# PROC091F_CAN_INTERFACE.net
KiCad netlist of a schematic drawn in Altium Designer
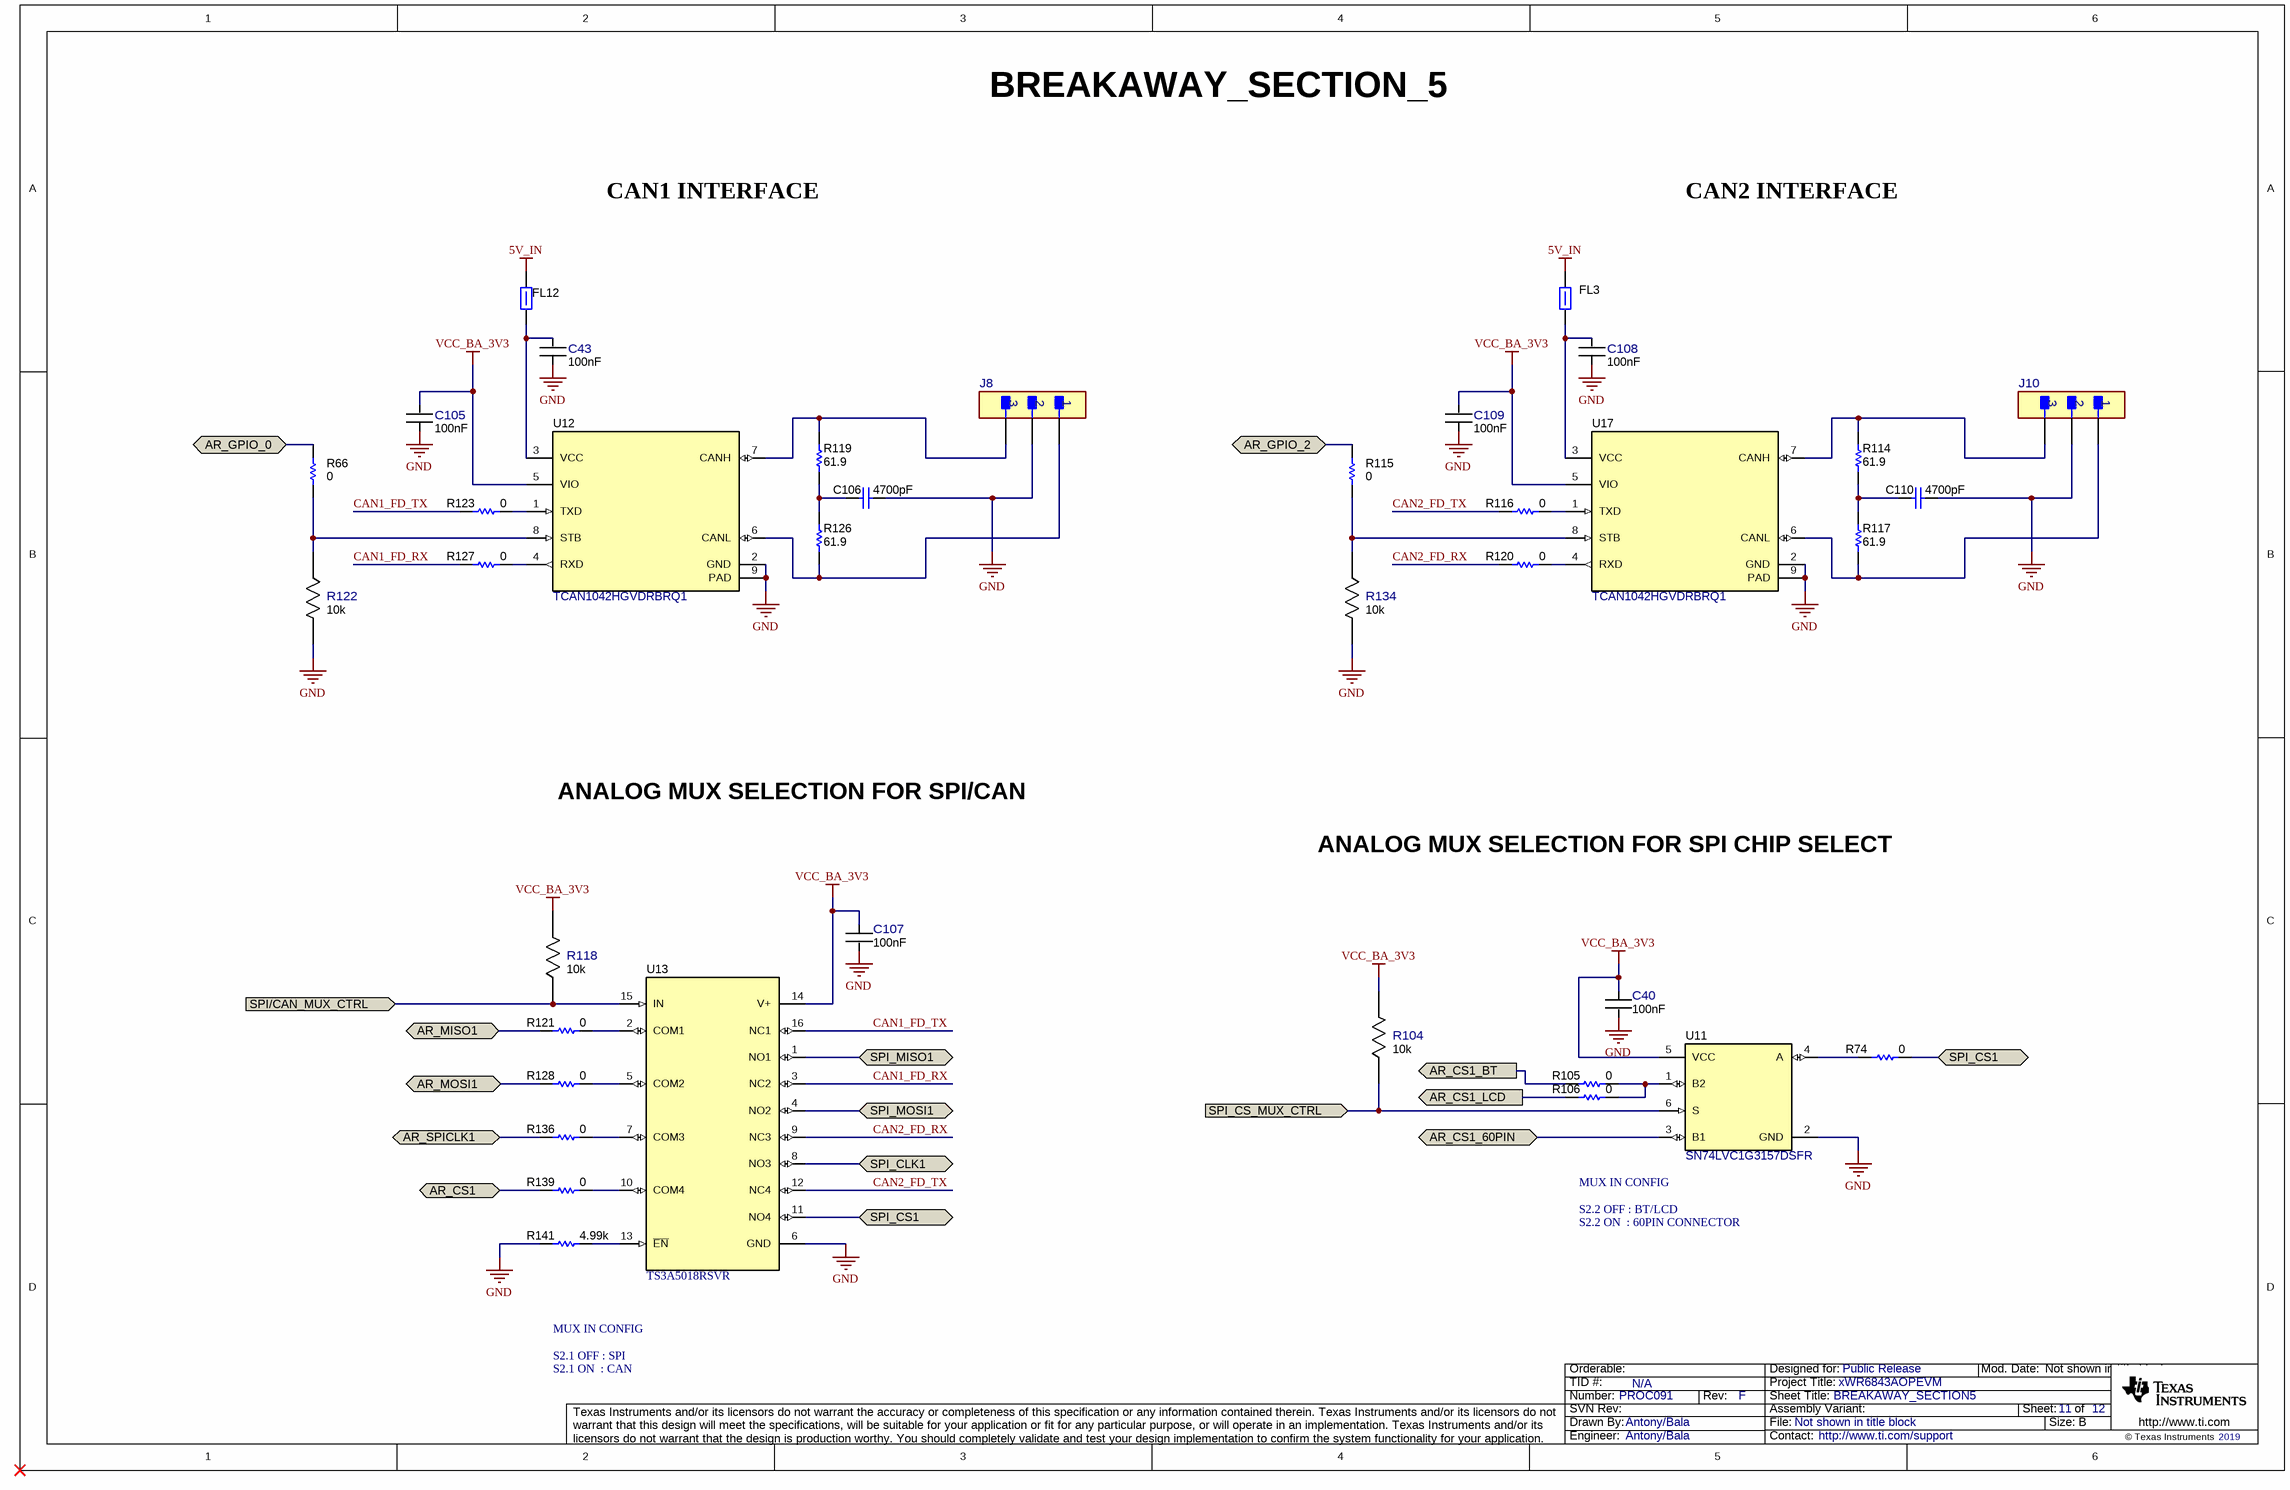
[diagram p0: PROC091F_CAN_INTERFACE.SchDoc]

(export (version "E")
  (design (tool "Eeschema 10.0.6"))
  (components
    (comp (ref "C40")
      (value "GRM033R6YA104KE14D")
      (footprint "FP-GRM033R6YA104KE14D_0201 (0603 Metric)-IPC_C")
      (description "Cap Ceramic 0.1uF 35V X5R 10% Pad SMD 0201 85C T/R")
      (fields (field (name "CAP_F") "100nF") (field (name "MANUFACTURER") "Murata Electronics North America"))
      (libsource (lib "Altium Vault - TI") (part "SYM-B32642B0223J"))
    )
    (comp (ref "C43")
      (value "GRM033R6YA104KE14D")
      (footprint "FP-GRM033R6YA104KE14D_0201 (0603 Metric)-IPC_C")
      (description "Cap Ceramic 0.1uF 35V X5R 10% Pad SMD 0201 85C T/R")
      (fields (field (name "CAP_F") "100nF") (field (name "MANUFACTURER") "Murata Electronics North America"))
      (libsource (lib "Altium Vault - TI") (part "SYM-B32642B0223J"))
    )
    (comp (ref "C105")
      (value "GRM033R6YA104KE14D")
      (footprint "FP-GRM033R6YA104KE14D_0201 (0603 Metric)-IPC_C")
      (description "Cap Ceramic 0.1uF 35V X5R 10% Pad SMD 0201 85C T/R")
      (fields (field (name "CAP_F") "100nF") (field (name "MANUFACTURER") "Murata Electronics North America"))
      (libsource (lib "Altium Vault - TI") (part "SYM-B32642B0223J"))
    )
    (comp (ref "C106")
      (value "GRM155R71H472KA01D")
      (footprint "0402L")
      (description "CAP, CERM, 4700 pF, 50 V, +/- 10%, X7R, 0402")
      (fields
        (field (name "MANUFACTURER") "MuRata")
        (field (name "VALUEDISPLAYED") "4700pF")
        (field (name "PUBLISHER") "Texas Instruments")
      )
      (libsource (lib "Altium Vault - TI") (part "Capacitor"))
    )
    (comp (ref "C107")
      (value "GRM033R6YA104KE14D")
      (footprint "FP-GRM033R6YA104KE14D_0201 (0603 Metric)-IPC_C")
      (description "Cap Ceramic 0.1uF 35V X5R 10% Pad SMD 0201 85C T/R")
      (fields (field (name "CAP_F") "100nF") (field (name "MANUFACTURER") "Murata Electronics North America"))
      (libsource (lib "Altium Vault - TI") (part "SYM-B32642B0223J"))
    )
    (comp (ref "C108")
      (value "GRM033R6YA104KE14D")
      (footprint "FP-GRM033R6YA104KE14D_0201 (0603 Metric)-IPC_C")
      (description "Cap Ceramic 0.1uF 35V X5R 10% Pad SMD 0201 85C T/R")
      (fields (field (name "CAP_F") "100nF") (field (name "MANUFACTURER") "Murata Electronics North America"))
      (libsource (lib "Altium Vault - TI") (part "SYM-B32642B0223J"))
    )
    (comp (ref "C109")
      (value "GRM033R6YA104KE14D")
      (footprint "FP-GRM033R6YA104KE14D_0201 (0603 Metric)-IPC_C")
      (description "Cap Ceramic 0.1uF 35V X5R 10% Pad SMD 0201 85C T/R")
      (fields (field (name "CAP_F") "100nF") (field (name "MANUFACTURER") "Murata Electronics North America"))
      (libsource (lib "Altium Vault - TI") (part "SYM-B32642B0223J"))
    )
    (comp (ref "C110")
      (value "GRM155R71H472KA01D")
      (footprint "0402L")
      (description "CAP, CERM, 4700 pF, 50 V, +/- 10%, X7R, 0402")
      (fields
        (field (name "MANUFACTURER") "MuRata")
        (field (name "VALUEDISPLAYED") "4700pF")
        (field (name "PUBLISHER") "Texas Instruments")
      )
      (libsource (lib "Altium Vault - TI") (part "Capacitor"))
    )
    (comp (ref "FL3")
      (value "BLM15PD300SZ1D")
      (footprint "0402L")
      (description "Inductor, Ferrite Bead, Ferrite, 2.2 A, 0.035 ohm, AEC-Q200 Grade 1, SMD")
      (fields (field (name "MANUFACTURER") "MuRata") (field (name "PUBLISHER") "Texas Instruments"))
      (libsource (lib "Altium Vault - TI") (part "Ferrite_Bead"))
    )
    (comp (ref "FL12")
      (value "BLM15PD300SZ1D")
      (footprint "0402L")
      (description "Inductor, Ferrite Bead, Ferrite, 2.2 A, 0.035 ohm, AEC-Q200 Grade 1, SMD")
      (fields (field (name "MANUFACTURER") "MuRata") (field (name "PUBLISHER") "Texas Instruments"))
      (libsource (lib "Altium Vault - TI") (part "Ferrite_Bead"))
    )
    (comp (ref "J8")
      (value "M50-3930342")
      (footprint "FP-M50-3930342_HDR3-MFG")
      (description "CONN HEADER R/A 3POS 1.27MM")
      (fields (field (name "MANUFACTURER") "Harwin"))
      (libsource (lib "Altium Vault - TI") (part "SYM-M50-3930342"))
    )
    (comp (ref "J10")
      (value "M50-3930342")
      (footprint "FP-M50-3930342_HDR3-MFG")
      (description "CONN HEADER R/A 3POS 1.27MM")
      (fields (field (name "MANUFACTURER") "Harwin"))
      (libsource (lib "Altium Vault - TI") (part "SYM-M50-3930342"))
    )
    (comp (ref "R66")
      (value "RC0201JR-070RL")
      (footprint "FP-RC0201JR-070RL_0201 (0603 Metric)-IPC_C")
      (description "RES SMD 0 OHM JUMPER 1/20W 0201")
      (fields (field (name "MANUFACTURER") "Yageo") (field (name "RES_OHM") "0"))
      (libsource (lib "Altium Vault - TI") (part "SYM-WSR3R1500F"))
    )
    (comp (ref "R74")
      (value "RC0201JR-070RL")
      (footprint "FP-RC0201JR-070RL_0201 (0603 Metric)-IPC_C")
      (description "RES SMD 0 OHM JUMPER 1/20W 0201")
      (fields (field (name "MANUFACTURER") "Yageo") (field (name "RES_OHM") "0"))
      (libsource (lib "Altium Vault - TI") (part "SYM-WSR3R1500F"))
    )
    (comp (ref "R104")
      (value "RR0306P-103-D")
      (footprint "FP-RR0306P-103-D_0201-IPC_C")
      (description "10 kOhms ±0.5% 0.05W, 1/20W Chip Resistor 0201 (0603 Metric)  Thin Film")
      (fields (field (name "MANUFACTURER") "Susumu") (field (name "RES_OHM") "10k"))
      (libsource (lib "Altium Vault - TI") (part "SYM-PMR18EZPJ000"))
    )
    (comp (ref "R105")
      (value "RC0201JR-070RL")
      (footprint "FP-RC0201JR-070RL_0201 (0603 Metric)-IPC_C")
      (description "RES SMD 0 OHM JUMPER 1/20W 0201")
      (fields (field (name "MANUFACTURER") "Yageo") (field (name "RES_OHM") "0"))
      (libsource (lib "Altium Vault - TI") (part "SYM-WSR3R1500F"))
    )
    (comp (ref "R106")
      (value "RC0201JR-070RL")
      (footprint "FP-RC0201JR-070RL_0201 (0603 Metric)-IPC_C")
      (description "RES SMD 0 OHM JUMPER 1/20W 0201")
      (fields (field (name "MANUFACTURER") "Yageo") (field (name "RES_OHM") "0"))
      (libsource (lib "Altium Vault - TI") (part "SYM-WSR3R1500F"))
    )
    (comp (ref "R114")
      (value "CRCW040261R9FKED")
      (footprint "0402L")
      (description "RES, 61.9, 1%, 0.063 W, AEC-Q200 Grade 0, 0402")
      (fields (field (name "MANUFACTURER") "Vishay-Dale") (field (name "VALUEDISPLAYED") "61.9"))
      (libsource (lib "Altium Vault - TI") (part "Resistor"))
    )
    (comp (ref "R115")
      (value "RC0201JR-070RL")
      (footprint "FP-RC0201JR-070RL_0201 (0603 Metric)-IPC_C")
      (description "RES SMD 0 OHM JUMPER 1/20W 0201")
      (fields (field (name "MANUFACTURER") "Yageo") (field (name "RES_OHM") "0"))
      (libsource (lib "Altium Vault - TI") (part "SYM-WSR3R1500F"))
    )
    (comp (ref "R116")
      (value "RC0201JR-070RL")
      (footprint "FP-RC0201JR-070RL_0201 (0603 Metric)-IPC_C")
      (description "RES SMD 0 OHM JUMPER 1/20W 0201")
      (fields (field (name "MANUFACTURER") "Yageo") (field (name "RES_OHM") "0"))
      (libsource (lib "Altium Vault - TI") (part "SYM-WSR3R1500F"))
    )
    (comp (ref "R117")
      (value "CRCW040261R9FKED")
      (footprint "0402L")
      (description "RES, 61.9, 1%, 0.063 W, AEC-Q200 Grade 0, 0402")
      (fields (field (name "MANUFACTURER") "Vishay-Dale") (field (name "VALUEDISPLAYED") "61.9"))
      (libsource (lib "Altium Vault - TI") (part "Resistor"))
    )
    (comp (ref "R118")
      (value "RR0306P-103-D")
      (footprint "FP-RR0306P-103-D_0201-IPC_C")
      (description "10 kOhms ±0.5% 0.05W, 1/20W Chip Resistor 0201 (0603 Metric)  Thin Film")
      (fields (field (name "MANUFACTURER") "Susumu") (field (name "RES_OHM") "10k"))
      (libsource (lib "Altium Vault - TI") (part "SYM-PMR18EZPJ000"))
    )
    (comp (ref "R119")
      (value "CRCW040261R9FKED")
      (footprint "0402L")
      (description "RES, 61.9, 1%, 0.063 W, AEC-Q200 Grade 0, 0402")
      (fields (field (name "MANUFACTURER") "Vishay-Dale") (field (name "VALUEDISPLAYED") "61.9"))
      (libsource (lib "Altium Vault - TI") (part "Resistor"))
    )
    (comp (ref "R120")
      (value "RC0201JR-070RL")
      (footprint "FP-RC0201JR-070RL_0201 (0603 Metric)-IPC_C")
      (description "RES SMD 0 OHM JUMPER 1/20W 0201")
      (fields (field (name "MANUFACTURER") "Yageo") (field (name "RES_OHM") "0"))
      (libsource (lib "Altium Vault - TI") (part "SYM-WSR3R1500F"))
    )
    (comp (ref "R121")
      (value "RC0201JR-070RL")
      (footprint "FP-RC0201JR-070RL_0201 (0603 Metric)-IPC_C")
      (description "RES SMD 0 OHM JUMPER 1/20W 0201")
      (fields (field (name "MANUFACTURER") "Yageo") (field (name "RES_OHM") "0"))
      (libsource (lib "Altium Vault - TI") (part "SYM-WSR3R1500F"))
    )
    (comp (ref "R122")
      (value "RR0306P-103-D")
      (footprint "FP-RR0306P-103-D_0201-IPC_C")
      (description "10 kOhms ±0.5% 0.05W, 1/20W Chip Resistor 0201 (0603 Metric)  Thin Film")
      (fields (field (name "MANUFACTURER") "Susumu") (field (name "RES_OHM") "10k"))
      (libsource (lib "Altium Vault - TI") (part "SYM-PMR18EZPJ000"))
    )
    (comp (ref "R123")
      (value "RC0201JR-070RL")
      (footprint "FP-RC0201JR-070RL_0201 (0603 Metric)-IPC_C")
      (description "RES SMD 0 OHM JUMPER 1/20W 0201")
      (fields (field (name "MANUFACTURER") "Yageo") (field (name "RES_OHM") "0"))
      (libsource (lib "Altium Vault - TI") (part "SYM-WSR3R1500F"))
    )
    (comp (ref "R126")
      (value "CRCW040261R9FKED")
      (footprint "0402L")
      (description "RES, 61.9, 1%, 0.063 W, AEC-Q200 Grade 0, 0402")
      (fields (field (name "MANUFACTURER") "Vishay-Dale") (field (name "VALUEDISPLAYED") "61.9"))
      (libsource (lib "Altium Vault - TI") (part "Resistor"))
    )
    (comp (ref "R127")
      (value "RC0201JR-070RL")
      (footprint "FP-RC0201JR-070RL_0201 (0603 Metric)-IPC_C")
      (description "RES SMD 0 OHM JUMPER 1/20W 0201")
      (fields (field (name "MANUFACTURER") "Yageo") (field (name "RES_OHM") "0"))
      (libsource (lib "Altium Vault - TI") (part "SYM-WSR3R1500F"))
    )
    (comp (ref "R128")
      (value "RC0201JR-070RL")
      (footprint "FP-RC0201JR-070RL_0201 (0603 Metric)-IPC_C")
      (description "RES SMD 0 OHM JUMPER 1/20W 0201")
      (fields (field (name "MANUFACTURER") "Yageo") (field (name "RES_OHM") "0"))
      (libsource (lib "Altium Vault - TI") (part "SYM-WSR3R1500F"))
    )
    (comp (ref "R134")
      (value "RR0306P-103-D")
      (footprint "FP-RR0306P-103-D_0201-IPC_C")
      (description "10 kOhms ±0.5% 0.05W, 1/20W Chip Resistor 0201 (0603 Metric)  Thin Film")
      (fields (field (name "MANUFACTURER") "Susumu") (field (name "RES_OHM") "10k"))
      (libsource (lib "Altium Vault - TI") (part "SYM-PMR18EZPJ000"))
    )
    (comp (ref "R136")
      (value "RC0201JR-070RL")
      (footprint "FP-RC0201JR-070RL_0201 (0603 Metric)-IPC_C")
      (description "RES SMD 0 OHM JUMPER 1/20W 0201")
      (fields (field (name "MANUFACTURER") "Yageo") (field (name "RES_OHM") "0"))
      (libsource (lib "Altium Vault - TI") (part "SYM-WSR3R1500F"))
    )
    (comp (ref "R139")
      (value "RC0201JR-070RL")
      (footprint "FP-RC0201JR-070RL_0201 (0603 Metric)-IPC_C")
      (description "RES SMD 0 OHM JUMPER 1/20W 0201")
      (fields (field (name "MANUFACTURER") "Yageo") (field (name "RES_OHM") "0"))
      (libsource (lib "Altium Vault - TI") (part "SYM-WSR3R1500F"))
    )
    (comp (ref "R141")
      (value "4.99k")
      (footprint "0201L")
      (description "RES, 4.99 k, 1%, 0.05 W, 0201")
      (fields
        (field (name "MANUFACTURER") "Yageo America")
        (field (name "PARTNUMBER") "RC0201FR-074K99L")
        (field (name "PUBLISHER") "Texas Instruments")
      )
      (libsource (lib "Altium Vault - TI") (part "Resistor"))
    )
    (comp (ref "U11")
      (value "SN74LVC1G3157DSFR")
      (footprint "DSF0006A")
      (description "1-Channel, 2:1 Analog Switch, DSF0006A (X2SON-6)")
      (fields
        (field (name "GENERIC PART NUMBER") "SN74LVC1G3157")
        (field (name "MANUFACTURER") "Texas Instruments")
      )
      (libsource (lib "Altium Vault - TI") (part "SN74LVC1G3157"))
    )
    (comp (ref "U12")
      (value "TCAN1042HGVDRBRQ1")
      (footprint "DRB0008F")
      (description "Automotive Fault Protected CAN Transceiver With Flexible Data-Rate, DRB0008F (VSON-8)")
      (fields
        (field (name "MANUFACTURER") "Texas Instruments")
        (field (name "ALTERNATE PARTNUMBER") "TCAN1042HGVDRBTQ1")
      )
      (libsource (lib "Altium Vault - TI") (part "TCAN1042DRB_V"))
    )
    (comp (ref "U13")
      (value "TS3A5018RSVR")
      (footprint "RSV0016A")
      (description "10-Ohm Quad SPDT Analog Switch, RSV0016A (UQFN-16)")
      (fields
        (field (name "MANUFACTURER") "Texas Instruments")
        (field (name "PARTNUMBER") "TS3A5018RSVR")
        (field (name "PUBLISHER") "Texas Instruments")
      )
      (libsource (lib "Altium Vault - TI") (part "TS3A5018RSV"))
    )
    (comp (ref "U17")
      (value "TCAN1042HGVDRBRQ1")
      (footprint "DRB0008F")
      (description "Automotive Fault Protected CAN Transceiver With Flexible Data-Rate, DRB0008F (VSON-8)")
      (fields
        (field (name "MANUFACTURER") "Texas Instruments")
        (field (name "ALTERNATE PARTNUMBER") "TCAN1042HGVDRBTQ1")
      )
      (libsource (lib "Altium Vault - TI") (part "TCAN1042DRB_V"))
    )
  )
  (nets
    (net (code "1") (name "/AR_CS1") (class "Default")
      (node (ref "R139") (pin "2") (pinfunction "2_2") (pintype "passive"))
    )
    (net (code "2") (name "/AR_CS1_60PIN") (class "Default")
      (node (ref "U11") (pin "3") (pinfunction "B1_3") (pintype "bidirectional"))
    )
    (net (code "3") (name "/AR_CS1_BT") (class "Default")
      (node (ref "R105") (pin "2") (pinfunction "2_2") (pintype "passive"))
    )
    (net (code "4") (name "/AR_CS1_LCD") (class "Default")
      (node (ref "R106") (pin "2") (pinfunction "2_2") (pintype "passive"))
    )
    (net (code "5") (name "/AR_GPIO_0") (class "Default")
      (node (ref "R66") (pin "1") (pinfunction "1_1") (pintype "passive"))
    )
    (net (code "6") (name "/AR_GPIO_2") (class "Default")
      (node (ref "R115") (pin "1") (pinfunction "1_1") (pintype "passive"))
    )
    (net (code "7") (name "/AR_MISO1") (class "Default")
      (node (ref "R121") (pin "2") (pinfunction "2_2") (pintype "passive"))
    )
    (net (code "8") (name "/AR_MOSI1") (class "Default")
      (node (ref "R128") (pin "2") (pinfunction "2_2") (pintype "passive"))
    )
    (net (code "9") (name "/AR_SPICLK1") (class "Default")
      (node (ref "R136") (pin "2") (pinfunction "2_2") (pintype "passive"))
    )
    (net (code "10") (name "/CAN1_FD_RX") (class "Default")
      (node (ref "R127") (pin "2") (pinfunction "2_2") (pintype "passive"))
      (node (ref "U13") (pin "3") (pinfunction "NC2_3") (pintype "bidirectional"))
    )
    (net (code "11") (name "/CAN1_FD_TX") (class "Default")
      (node (ref "R123") (pin "2") (pinfunction "2_2") (pintype "passive"))
      (node (ref "U13") (pin "16") (pinfunction "NC1_16") (pintype "bidirectional"))
    )
    (net (code "12") (name "/CAN2_FD_RX") (class "Default")
      (node (ref "R120") (pin "2") (pinfunction "2_2") (pintype "passive"))
      (node (ref "U13") (pin "9") (pinfunction "NC3_9") (pintype "bidirectional"))
    )
    (net (code "13") (name "/CAN2_FD_TX") (class "Default")
      (node (ref "R116") (pin "2") (pinfunction "2_2") (pintype "passive"))
      (node (ref "U13") (pin "12") (pinfunction "NC4_12") (pintype "bidirectional"))
    )
    (net (code "14") (name "/SPI_CLK1") (class "Default")
      (node (ref "U13") (pin "8") (pinfunction "NO3_8") (pintype "bidirectional"))
    )
    (net (code "15") (name "/SPI_CS1") (class "Default")
      (node (ref "R74") (pin "1") (pinfunction "1_1") (pintype "passive"))
      (node (ref "U13") (pin "11") (pinfunction "NO4_11") (pintype "bidirectional"))
    )
    (net (code "16") (name "/SPI_CS_MUX_CTRL") (class "Default")
      (node (ref "R104") (pin "1") (pinfunction "1_1") (pintype "passive"))
      (node (ref "U11") (pin "6") (pinfunction "S_6") (pintype "input"))
    )
    (net (code "17") (name "/SPI_MISO1") (class "Default")
      (node (ref "U13") (pin "1") (pinfunction "NO1_1") (pintype "bidirectional"))
    )
    (net (code "18") (name "/SPI_MOSI1") (class "Default")
      (node (ref "U13") (pin "4") (pinfunction "NO2_4") (pintype "bidirectional"))
    )
    (net (code "19") (name "/SPI{slash}CAN_MUX_CTRL") (class "Default")
      (node (ref "R118") (pin "1") (pinfunction "1_1") (pintype "passive"))
      (node (ref "U13") (pin "15") (pinfunction "IN_15") (pintype "input"))
    )
    (net (code "20") (name "5V_IN") (class "Default")
      (node (ref "FL12") (pin "2") (pinfunction "2_2") (pintype "passive"))
      (node (ref "FL3") (pin "2") (pinfunction "2_2") (pintype "passive"))
    )
    (net (code "21") (name "GND") (class "Default")
      (node (ref "C105") (pin "1") (pinfunction "1_1") (pintype "passive"))
      (node (ref "C106") (pin "1") (pinfunction "1_1") (pintype "passive"))
      (node (ref "C107") (pin "2") (pinfunction "2_2") (pintype "passive"))
      (node (ref "C108") (pin "1") (pinfunction "1_1") (pintype "passive"))
      (node (ref "C109") (pin "1") (pinfunction "1_1") (pintype "passive"))
      (node (ref "C110") (pin "1") (pinfunction "1_1") (pintype "passive"))
      (node (ref "C40") (pin "2") (pinfunction "2_2") (pintype "passive"))
      (node (ref "C43") (pin "1") (pinfunction "1_1") (pintype "passive"))
      (node (ref "J10") (pin "2") (pinfunction "2_2") (pintype "passive"))
      (node (ref "J8") (pin "2") (pinfunction "2_2") (pintype "passive"))
      (node (ref "R122") (pin "2") (pinfunction "2_2") (pintype "passive"))
      (node (ref "R134") (pin "2") (pinfunction "2_2") (pintype "passive"))
      (node (ref "R141") (pin "2") (pinfunction "2_2") (pintype "passive"))
      (node (ref "U11") (pin "2") (pinfunction "GND_2") (pintype "power_in"))
      (node (ref "U12") (pin "2") (pinfunction "GND_2") (pintype "power_in"))
      (node (ref "U12") (pin "9") (pinfunction "PAD_9") (pintype "power_in"))
      (node (ref "U13") (pin "6") (pinfunction "GND_6") (pintype "power_in"))
      (node (ref "U17") (pin "2") (pinfunction "GND_2") (pintype "power_in"))
      (node (ref "U17") (pin "9") (pinfunction "PAD_9") (pintype "power_in"))
    )
    (net (code "22") (name "Net-(C106-Pad2)") (class "Default")
      (node (ref "C106") (pin "2") (pinfunction "2_2") (pintype "passive"))
      (node (ref "R119") (pin "1") (pinfunction "1_1") (pintype "passive"))
      (node (ref "R126") (pin "2") (pinfunction "2_2") (pintype "passive"))
    )
    (net (code "23") (name "Net-(C110-Pad2)") (class "Default")
      (node (ref "C110") (pin "2") (pinfunction "2_2") (pintype "passive"))
      (node (ref "R114") (pin "1") (pinfunction "1_1") (pintype "passive"))
      (node (ref "R117") (pin "2") (pinfunction "2_2") (pintype "passive"))
    )
    (net (code "24") (name "Net-(U11-A)") (class "Default")
      (node (ref "R74") (pin "2") (pinfunction "2_2") (pintype "passive"))
      (node (ref "U11") (pin "4") (pinfunction "A_4") (pintype "bidirectional"))
    )
    (net (code "25") (name "Net-(U11-B2)") (class "Default")
      (node (ref "R105") (pin "1") (pinfunction "1_1") (pintype "passive"))
      (node (ref "R106") (pin "1") (pinfunction "1_1") (pintype "passive"))
      (node (ref "U11") (pin "1") (pinfunction "B2_1") (pintype "bidirectional"))
    )
    (net (code "26") (name "Net-(U12-CANH)") (class "Default")
      (node (ref "J8") (pin "3") (pinfunction "3_3") (pintype "passive"))
      (node (ref "R119") (pin "2") (pinfunction "2_2") (pintype "passive"))
      (node (ref "U12") (pin "7") (pinfunction "CANH_7") (pintype "bidirectional"))
    )
    (net (code "27") (name "Net-(U12-CANL)") (class "Default")
      (node (ref "J8") (pin "1") (pinfunction "1_1") (pintype "passive"))
      (node (ref "R126") (pin "1") (pinfunction "1_1") (pintype "passive"))
      (node (ref "U12") (pin "6") (pinfunction "CANL_6") (pintype "bidirectional"))
    )
    (net (code "28") (name "Net-(U12-RXD)") (class "Default")
      (node (ref "R127") (pin "1") (pinfunction "1_1") (pintype "passive"))
      (node (ref "U12") (pin "4") (pinfunction "RXD_4") (pintype "output"))
    )
    (net (code "29") (name "Net-(U12-STB)") (class "Default")
      (node (ref "R122") (pin "1") (pinfunction "1_1") (pintype "passive"))
      (node (ref "R66") (pin "2") (pinfunction "2_2") (pintype "passive"))
      (node (ref "U12") (pin "8") (pinfunction "STB_8") (pintype "input"))
    )
    (net (code "30") (name "Net-(U12-TXD)") (class "Default")
      (node (ref "R123") (pin "1") (pinfunction "1_1") (pintype "passive"))
      (node (ref "U12") (pin "1") (pinfunction "TXD_1") (pintype "input"))
    )
    (net (code "31") (name "Net-(U12-VCC)") (class "Default")
      (node (ref "C43") (pin "2") (pinfunction "2_2") (pintype "passive"))
      (node (ref "FL12") (pin "1") (pinfunction "1_1") (pintype "passive"))
      (node (ref "U12") (pin "3") (pinfunction "VCC_3") (pintype "power_in"))
    )
    (net (code "32") (name "Net-(U13-COM1)") (class "Default")
      (node (ref "R121") (pin "1") (pinfunction "1_1") (pintype "passive"))
      (node (ref "U13") (pin "2") (pinfunction "COM1_2") (pintype "bidirectional"))
    )
    (net (code "33") (name "Net-(U13-COM2)") (class "Default")
      (node (ref "R128") (pin "1") (pinfunction "1_1") (pintype "passive"))
      (node (ref "U13") (pin "5") (pinfunction "COM2_5") (pintype "bidirectional"))
    )
    (net (code "34") (name "Net-(U13-COM3)") (class "Default")
      (node (ref "R136") (pin "1") (pinfunction "1_1") (pintype "passive"))
      (node (ref "U13") (pin "7") (pinfunction "COM3_7") (pintype "bidirectional"))
    )
    (net (code "35") (name "Net-(U13-COM4)") (class "Default")
      (node (ref "R139") (pin "1") (pinfunction "1_1") (pintype "passive"))
      (node (ref "U13") (pin "10") (pinfunction "COM4_10") (pintype "bidirectional"))
    )
    (net (code "36") (name "Net-(U13-EN)") (class "Default")
      (node (ref "R141") (pin "1") (pinfunction "1_1") (pintype "passive"))
      (node (ref "U13") (pin "13") (pinfunction "EN_13") (pintype "input"))
    )
    (net (code "37") (name "Net-(U17-CANH)") (class "Default")
      (node (ref "J10") (pin "3") (pinfunction "3_3") (pintype "passive"))
      (node (ref "R114") (pin "2") (pinfunction "2_2") (pintype "passive"))
      (node (ref "U17") (pin "7") (pinfunction "CANH_7") (pintype "bidirectional"))
    )
    (net (code "38") (name "Net-(U17-CANL)") (class "Default")
      (node (ref "J10") (pin "1") (pinfunction "1_1") (pintype "passive"))
      (node (ref "R117") (pin "1") (pinfunction "1_1") (pintype "passive"))
      (node (ref "U17") (pin "6") (pinfunction "CANL_6") (pintype "bidirectional"))
    )
    (net (code "39") (name "Net-(U17-RXD)") (class "Default")
      (node (ref "R120") (pin "1") (pinfunction "1_1") (pintype "passive"))
      (node (ref "U17") (pin "4") (pinfunction "RXD_4") (pintype "output"))
    )
    (net (code "40") (name "Net-(U17-STB)") (class "Default")
      (node (ref "R115") (pin "2") (pinfunction "2_2") (pintype "passive"))
      (node (ref "R134") (pin "1") (pinfunction "1_1") (pintype "passive"))
      (node (ref "U17") (pin "8") (pinfunction "STB_8") (pintype "input"))
    )
    (net (code "41") (name "Net-(U17-TXD)") (class "Default")
      (node (ref "R116") (pin "1") (pinfunction "1_1") (pintype "passive"))
      (node (ref "U17") (pin "1") (pinfunction "TXD_1") (pintype "input"))
    )
    (net (code "42") (name "Net-(U17-VCC)") (class "Default")
      (node (ref "C108") (pin "2") (pinfunction "2_2") (pintype "passive"))
      (node (ref "FL3") (pin "1") (pinfunction "1_1") (pintype "passive"))
      (node (ref "U17") (pin "3") (pinfunction "VCC_3") (pintype "power_in"))
    )
    (net (code "43") (name "VCC_BA_3V3") (class "Default")
      (node (ref "C105") (pin "2") (pinfunction "2_2") (pintype "passive"))
      (node (ref "C107") (pin "1") (pinfunction "1_1") (pintype "passive"))
      (node (ref "C109") (pin "2") (pinfunction "2_2") (pintype "passive"))
      (node (ref "C40") (pin "1") (pinfunction "1_1") (pintype "passive"))
      (node (ref "R104") (pin "2") (pinfunction "2_2") (pintype "passive"))
      (node (ref "R118") (pin "2") (pinfunction "2_2") (pintype "passive"))
      (node (ref "U11") (pin "5") (pinfunction "VCC_5") (pintype "power_in"))
      (node (ref "U12") (pin "5") (pinfunction "VIO_5") (pintype "power_in"))
      (node (ref "U13") (pin "14") (pinfunction "V+_14") (pintype "power_in"))
      (node (ref "U17") (pin "5") (pinfunction "VIO_5") (pintype "power_in"))
    )
  )
)
